# controller_PS.net
KiCad netlist of a schematic drawn in EAGLE
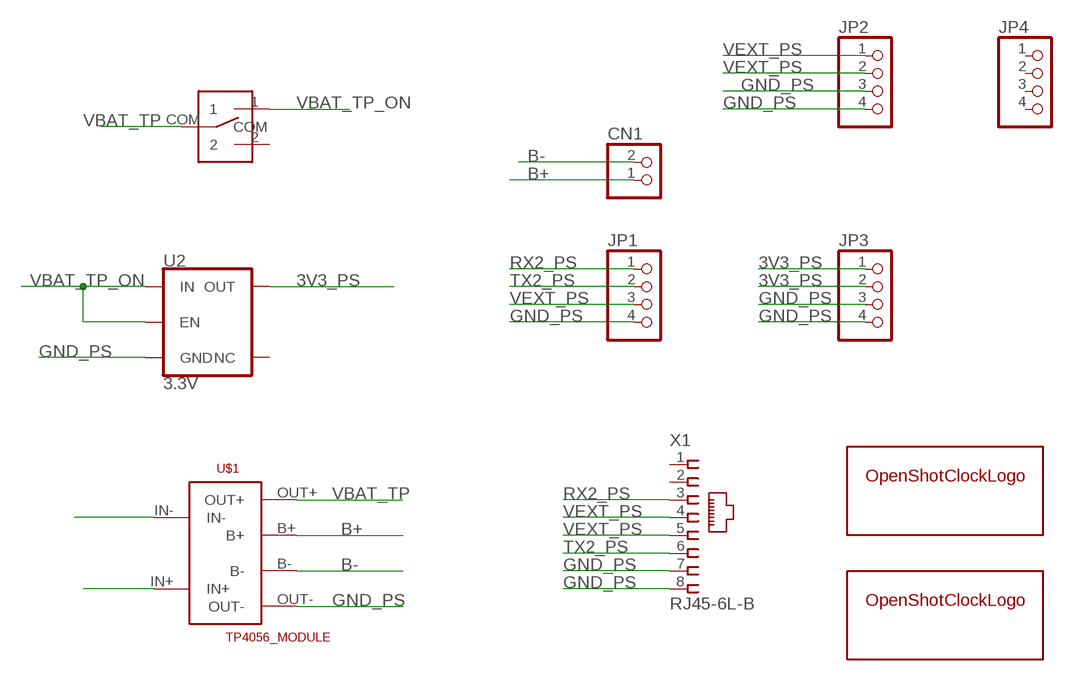
[diagram p0: schematic, sheet 1]

(export (version "E")
  (design (tool "Eeschema 10.0.6"))
  (components
    (comp (ref "CN1")
      (value "JST_2PIN-THM-RA")
      (footprint "eagle-import:JST-PH-2-THM-RA")
      (libsource (lib "eagle-import") (part "JST_2PIN-THM-RA"))
    )
    (comp (ref "JP1")
      (value "PINHD-1X4")
      (footprint "eagle-import:1X04")
      (libsource (lib "eagle-import") (part "PINHD-1X4"))
    )
    (comp (ref "JP2")
      (value "PINHD-1X4")
      (footprint "eagle-import:1X04")
      (libsource (lib "eagle-import") (part "PINHD-1X4"))
    )
    (comp (ref "JP3")
      (value "PINHD-1X4")
      (footprint "eagle-import:1X04")
      (libsource (lib "eagle-import") (part "PINHD-1X4"))
    )
    (comp (ref "JP4")
      (value "PINHD-1X4")
      (footprint "eagle-import:1X04")
      (libsource (lib "eagle-import") (part "PINHD-1X4"))
    )
    (comp (ref "U$1")
      (value "TP4056_MODULE")
      (footprint "eagle-import:TP4056_MODULE")
      (libsource (lib "eagle-import") (part "TP4056_MODULE"))
    )
    (comp (ref "U$3")
      (value "OPEN-SHOT-CLOCK-LOGOOSCL-SMALL")
      (footprint "eagle-import:OPEN-SHOT-CLOCK-LOGO-SMALL")
      (libsource (lib "eagle-import") (part "OPEN-SHOT-CLOCK-LOGOOSCL-SMALL"))
    )
    (comp (ref "U$4")
      (value "OPEN-SHOT-CLOCK-LOGOOSCL-SMALL")
      (footprint "eagle-import:OPEN-SHOT-CLOCK-LOGO-SMALL")
      (libsource (lib "eagle-import") (part "OPEN-SHOT-CLOCK-LOGOOSCL-SMALL"))
    )
    (comp (ref "U$6")
      (value "SK12D07VG4")
      (footprint "eagle-import:SK12D07VG4")
      (fields (field (name "MF") "C&K"))
      (libsource (lib "eagle-import") (part "SK12D07VG4"))
    )
    (comp (ref "U2")
      (value "3.3V")
      (footprint "eagle-import:SOT23-5")
      (libsource (lib "eagle-import") (part "V_REG_AP2112K-3.3V"))
    )
    (comp (ref "X1")
      (value "RJ45-6L-B")
      (footprint "eagle-import:RJ45-NO-SHIELD")
      (libsource (lib "eagle-import") (part "RJ45-6L-B"))
    )
  )
  (nets
    (net (code "1") (name "/3V3_PS") (class "Default")
      (node (ref "JP3") (pin "1") (pinfunction "1_1") (pintype "passive"))
      (node (ref "JP3") (pin "2") (pinfunction "2_2") (pintype "passive"))
      (node (ref "U2") (pin "5") (pinfunction "OUT_5") (pintype "passive"))
    )
    (net (code "2") (name "/B+") (class "Default")
      (node (ref "CN1") (pin "1") (pinfunction "2_1") (pintype "passive"))
      (node (ref "U$1") (pin "B+") (pinfunction "B+_B+") (pintype "bidirectional"))
    )
    (net (code "3") (name "/B-") (class "Default")
      (node (ref "CN1") (pin "2") (pinfunction "1_2") (pintype "passive"))
      (node (ref "U$1") (pin "B-") (pinfunction "B-_B-") (pintype "bidirectional"))
    )
    (net (code "4") (name "/GND_PS") (class "Default")
      (node (ref "JP1") (pin "4") (pinfunction "4_4") (pintype "passive"))
      (node (ref "JP2") (pin "3") (pinfunction "3_3") (pintype "passive"))
      (node (ref "JP2") (pin "4") (pinfunction "4_4") (pintype "passive"))
      (node (ref "JP3") (pin "3") (pinfunction "3_3") (pintype "passive"))
      (node (ref "JP3") (pin "4") (pinfunction "4_4") (pintype "passive"))
      (node (ref "U$1") (pin "OUT-") (pinfunction "OUT-_OUT-") (pintype "bidirectional"))
      (node (ref "U2") (pin "2") (pinfunction "GND_2") (pintype "input"))
      (node (ref "X1") (pin "7") (pinfunction "7_7") (pintype "passive"))
      (node (ref "X1") (pin "8") (pinfunction "8_8") (pintype "passive"))
    )
    (net (code "5") (name "/RX2_PS") (class "Default")
      (node (ref "JP1") (pin "1") (pinfunction "1_1") (pintype "passive"))
      (node (ref "X1") (pin "3") (pinfunction "3_3") (pintype "passive"))
    )
    (net (code "6") (name "/TX2_PS") (class "Default")
      (node (ref "JP1") (pin "2") (pinfunction "2_2") (pintype "passive"))
      (node (ref "X1") (pin "6") (pinfunction "6_6") (pintype "passive"))
    )
    (net (code "7") (name "/VBAT_TP") (class "Default")
      (node (ref "U$1") (pin "OUT+") (pinfunction "OUT+_OUT+") (pintype "bidirectional"))
      (node (ref "U$6") (pin "COM") (pinfunction "COM_COM") (pintype "bidirectional"))
    )
    (net (code "8") (name "/VBAT_TP_ON") (class "Default")
      (node (ref "U$6") (pin "1") (pinfunction "1_1") (pintype "bidirectional"))
      (node (ref "U2") (pin "1") (pinfunction "IN_1") (pintype "input"))
      (node (ref "U2") (pin "3") (pinfunction "EN_3") (pintype "input"))
    )
    (net (code "9") (name "/VEXT_PS") (class "Default")
      (node (ref "JP1") (pin "3") (pinfunction "3_3") (pintype "passive"))
      (node (ref "JP2") (pin "1") (pinfunction "1_1") (pintype "passive"))
      (node (ref "JP2") (pin "2") (pinfunction "2_2") (pintype "passive"))
      (node (ref "X1") (pin "4") (pinfunction "4_4") (pintype "passive"))
      (node (ref "X1") (pin "5") (pinfunction "5_5") (pintype "passive"))
    )
    (net (code "10") (name "unconnected-(JP4-Pad1)") (class "Default")
      (node (ref "JP4") (pin "1") (pinfunction "1_1") (pintype "passive"))
    )
    (net (code "11") (name "unconnected-(JP4-Pad2)") (class "Default")
      (node (ref "JP4") (pin "2") (pinfunction "2_2") (pintype "passive"))
    )
    (net (code "12") (name "unconnected-(JP4-Pad3)") (class "Default")
      (node (ref "JP4") (pin "3") (pinfunction "3_3") (pintype "passive"))
    )
    (net (code "13") (name "unconnected-(JP4-Pad4)") (class "Default")
      (node (ref "JP4") (pin "4") (pinfunction "4_4") (pintype "passive"))
    )
    (net (code "14") (name "unconnected-(U$1-PadIN+)") (class "Default")
      (node (ref "U$1") (pin "IN+") (pinfunction "IN+_IN+") (pintype "bidirectional"))
    )
    (net (code "15") (name "unconnected-(U$1-PadIN-)") (class "Default")
      (node (ref "U$1") (pin "IN-") (pinfunction "IN-_IN-") (pintype "bidirectional"))
    )
    (net (code "16") (name "unconnected-(U$6-Pad2)") (class "Default")
      (node (ref "U$6") (pin "2") (pinfunction "2_2") (pintype "bidirectional"))
    )
    (net (code "17") (name "unconnected-(U2-NC-Pad4)") (class "Default")
      (node (ref "U2") (pin "4") (pinfunction "NC_4") (pintype "no_connect"))
    )
    (net (code "18") (name "unconnected-(X1-Pad1)") (class "Default")
      (node (ref "X1") (pin "1") (pinfunction "1_1") (pintype "passive"))
    )
    (net (code "19") (name "unconnected-(X1-Pad2)") (class "Default")
      (node (ref "X1") (pin "2") (pinfunction "2_2") (pintype "passive"))
    )
  )
)
